# GBA_Modular_Matrix.net
KiCad netlist of a schematic drawn in EAGLE
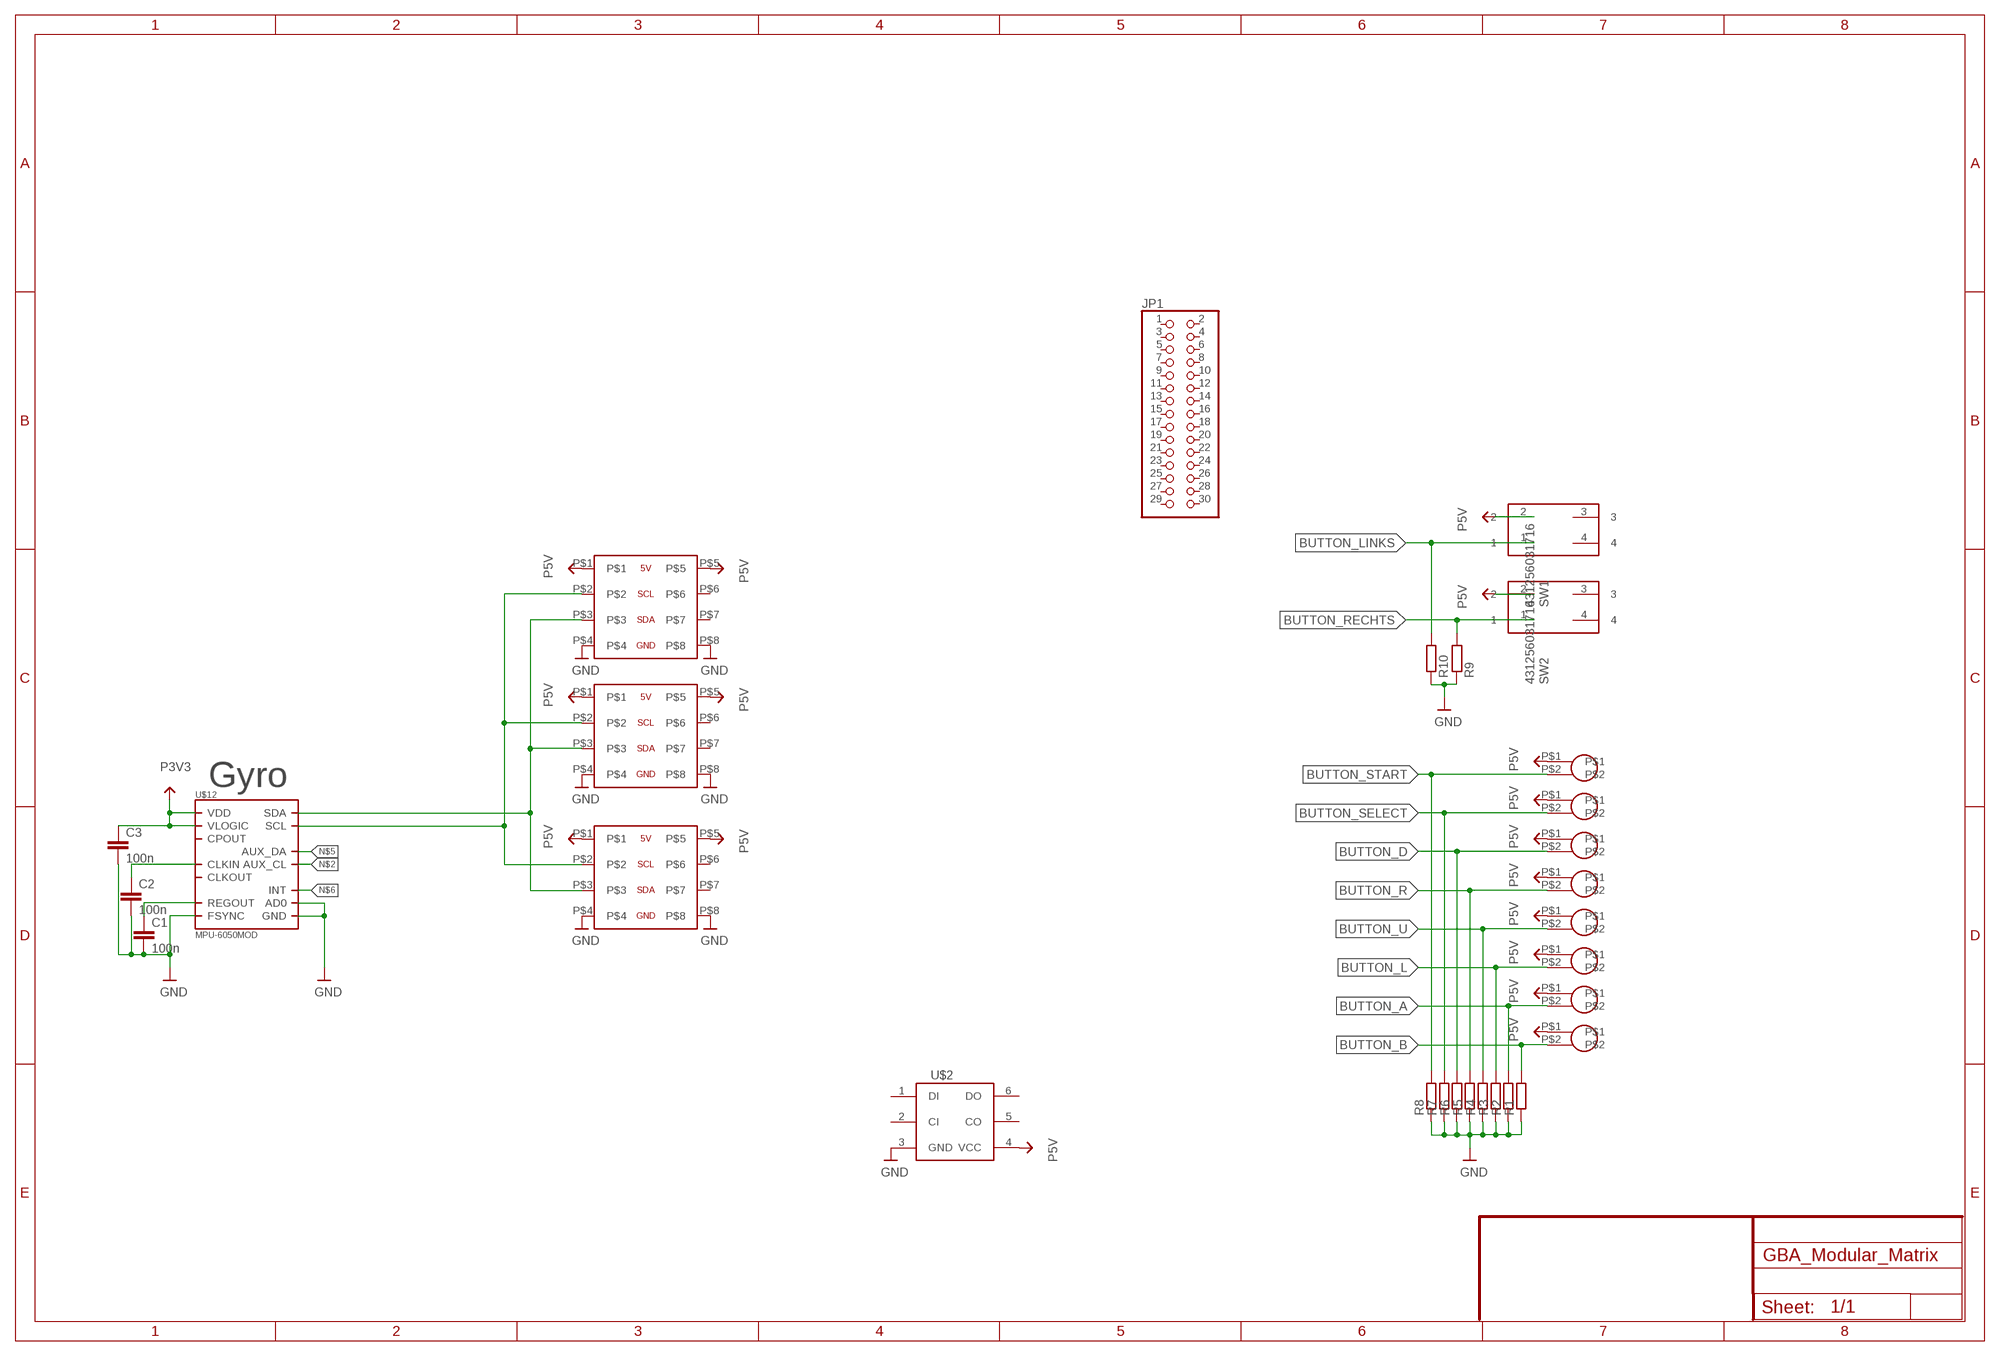
[diagram p0: schematic, sheet 1]

(export (version "E")
  (design (tool "Eeschema 10.0.6"))
  (components
    (comp (ref "C1")
      (value "100n")
      (footprint "eagle-import:C0603")
      (libsource (lib "eagle-import") (part "C-EUC0603"))
    )
    (comp (ref "C2")
      (value "100n")
      (footprint "eagle-import:C0603")
      (libsource (lib "eagle-import") (part "C-EUC0603"))
    )
    (comp (ref "C3")
      (value "100n")
      (footprint "eagle-import:C0603")
      (libsource (lib "eagle-import") (part "C-EUC0603"))
    )
    (comp (ref "JP1")
      (value "PINHD-2X15")
      (footprint "eagle-import:2X15")
      (libsource (lib "eagle-import") (part "PINHD-2X15"))
    )
    (comp (ref "R1")
      (value "R-EU_R0805")
      (footprint "eagle-import:R0805")
      (libsource (lib "eagle-import") (part "R-EU_R0805"))
    )
    (comp (ref "R2")
      (value "R-EU_R0805")
      (footprint "eagle-import:R0805")
      (libsource (lib "eagle-import") (part "R-EU_R0805"))
    )
    (comp (ref "R3")
      (value "R-EU_R0805")
      (footprint "eagle-import:R0805")
      (libsource (lib "eagle-import") (part "R-EU_R0805"))
    )
    (comp (ref "R4")
      (value "R-EU_R0805")
      (footprint "eagle-import:R0805")
      (libsource (lib "eagle-import") (part "R-EU_R0805"))
    )
    (comp (ref "R5")
      (value "R-EU_R0805")
      (footprint "eagle-import:R0805")
      (libsource (lib "eagle-import") (part "R-EU_R0805"))
    )
    (comp (ref "R6")
      (value "R-EU_R0805")
      (footprint "eagle-import:R0805")
      (libsource (lib "eagle-import") (part "R-EU_R0805"))
    )
    (comp (ref "R7")
      (value "R-EU_R0805")
      (footprint "eagle-import:R0805")
      (libsource (lib "eagle-import") (part "R-EU_R0805"))
    )
    (comp (ref "R8")
      (value "R-EU_R0805")
      (footprint "eagle-import:R0805")
      (libsource (lib "eagle-import") (part "R-EU_R0805"))
    )
    (comp (ref "R9")
      (value "R-EU_R0805")
      (footprint "eagle-import:R0805")
      (libsource (lib "eagle-import") (part "R-EU_R0805"))
    )
    (comp (ref "R10")
      (value "R-EU_R0805")
      (footprint "eagle-import:R0805")
      (libsource (lib "eagle-import") (part "R-EU_R0805"))
    )
    (comp (ref "SW1")
      (value "431256031716")
      (footprint "eagle-import:431256031716")
      (libsource (lib "eagle-import") (part "431256031716"))
    )
    (comp (ref "SW2")
      (value "431256031716")
      (footprint "eagle-import:431256031716")
      (libsource (lib "eagle-import") (part "431256031716"))
    )
    (comp (ref "U$2")
      (value "APA102")
      (footprint "eagle-import:LED5050")
      (libsource (lib "eagle-import") (part "APA102"))
    )
    (comp (ref "U$4")
      (value "GBA_BUTTONAB")
      (footprint "eagle-import:GBA_AB")
      (libsource (lib "eagle-import") (part "GBA_BUTTONAB"))
    )
    (comp (ref "U$5")
      (value "GBA_BUTTONAB")
      (footprint "eagle-import:GBA_AB")
      (libsource (lib "eagle-import") (part "GBA_BUTTONAB"))
    )
    (comp (ref "U$6")
      (value "GBA_BUTTONDIREKTION")
      (footprint "eagle-import:GBA_DIREKTION")
      (libsource (lib "eagle-import") (part "GBA_BUTTONDIREKTION"))
    )
    (comp (ref "U$7")
      (value "GBA_BUTTONDIREKTION")
      (footprint "eagle-import:GBA_DIREKTION")
      (libsource (lib "eagle-import") (part "GBA_BUTTONDIREKTION"))
    )
    (comp (ref "U$8")
      (value "GBA_BUTTONDIREKTION")
      (footprint "eagle-import:GBA_DIREKTION")
      (libsource (lib "eagle-import") (part "GBA_BUTTONDIREKTION"))
    )
    (comp (ref "U$9")
      (value "GBA_BUTTONDIREKTION")
      (footprint "eagle-import:GBA_DIREKTION")
      (libsource (lib "eagle-import") (part "GBA_BUTTONDIREKTION"))
    )
    (comp (ref "U$10")
      (value "GBA_BUTTONSTART")
      (footprint "eagle-import:GBA_START")
      (libsource (lib "eagle-import") (part "GBA_BUTTONSTART"))
    )
    (comp (ref "U$11")
      (value "GBA_BUTTONSTART")
      (footprint "eagle-import:GBA_START")
      (libsource (lib "eagle-import") (part "GBA_BUTTONSTART"))
    )
    (comp (ref "U$12")
      (value "MPU-6050MOD")
      (footprint "eagle-import:QFN.24.4X4.MOD")
      (libsource (lib "eagle-import") (part "MPU-6050MOD"))
    )
    (comp (ref "U$18")
      (value "DEBAUER_18X6MATRIX")
      (footprint "eagle-import:DEBAUER_16X8MATRIX")
      (libsource (lib "eagle-import") (part "DEBAUER_18X6MATRIX"))
    )
    (comp (ref "U$19")
      (value "DEBAUER_18X6MATRIX")
      (footprint "eagle-import:DEBAUER_16X8MATRIX")
      (libsource (lib "eagle-import") (part "DEBAUER_18X6MATRIX"))
    )
    (comp (ref "U$20")
      (value "DEBAUER_18X6MATRIX")
      (footprint "eagle-import:DEBAUER_16X8MATRIX")
      (libsource (lib "eagle-import") (part "DEBAUER_18X6MATRIX"))
    )
  )
  (nets
    (net (code "1") (name "BUTTON_A") (class "Default")
      (node (ref "R2") (pin "2") (pinfunction "2_2") (pintype "passive"))
      (node (ref "U$4") (pin "P$2") (pinfunction "P$2_P$2") (pintype "bidirectional"))
    )
    (net (code "2") (name "BUTTON_B") (class "Default")
      (node (ref "R1") (pin "2") (pinfunction "2_2") (pintype "passive"))
      (node (ref "U$5") (pin "P$2") (pinfunction "P$2_P$2") (pintype "bidirectional"))
    )
    (net (code "3") (name "BUTTON_D") (class "Default")
      (node (ref "R6") (pin "2") (pinfunction "2_2") (pintype "passive"))
      (node (ref "U$6") (pin "P$2") (pinfunction "P$2_P$2") (pintype "bidirectional"))
    )
    (net (code "4") (name "BUTTON_L") (class "Default")
      (node (ref "R3") (pin "2") (pinfunction "2_2") (pintype "passive"))
      (node (ref "U$9") (pin "P$2") (pinfunction "P$2_P$2") (pintype "bidirectional"))
    )
    (net (code "5") (name "BUTTON_LINKS") (class "Default")
      (node (ref "R10") (pin "2") (pinfunction "2_2") (pintype "passive"))
      (node (ref "SW1") (pin "1") (pinfunction "1_1") (pintype "bidirectional"))
    )
    (net (code "6") (name "BUTTON_R") (class "Default")
      (node (ref "R5") (pin "2") (pinfunction "2_2") (pintype "passive"))
      (node (ref "U$7") (pin "P$2") (pinfunction "P$2_P$2") (pintype "bidirectional"))
    )
    (net (code "7") (name "BUTTON_RECHTS") (class "Default")
      (node (ref "R9") (pin "2") (pinfunction "2_2") (pintype "passive"))
      (node (ref "SW2") (pin "1") (pinfunction "1_1") (pintype "bidirectional"))
    )
    (net (code "8") (name "BUTTON_SELECT") (class "Default")
      (node (ref "R7") (pin "2") (pinfunction "2_2") (pintype "passive"))
      (node (ref "U$11") (pin "P$2") (pinfunction "P$2_P$2") (pintype "bidirectional"))
    )
    (net (code "9") (name "BUTTON_START") (class "Default")
      (node (ref "R8") (pin "2") (pinfunction "2_2") (pintype "passive"))
      (node (ref "U$10") (pin "P$2") (pinfunction "P$2_P$2") (pintype "bidirectional"))
    )
    (net (code "10") (name "BUTTON_U") (class "Default")
      (node (ref "R4") (pin "2") (pinfunction "2_2") (pintype "passive"))
      (node (ref "U$8") (pin "P$2") (pinfunction "P$2_P$2") (pintype "bidirectional"))
    )
    (net (code "11") (name "GND") (class "Default")
      (node (ref "C1") (pin "2") (pinfunction "2_2") (pintype "passive"))
      (node (ref "C2") (pin "2") (pinfunction "2_2") (pintype "passive"))
      (node (ref "C3") (pin "2") (pinfunction "2_2") (pintype "passive"))
      (node (ref "R1") (pin "1") (pinfunction "1_1") (pintype "passive"))
      (node (ref "R10") (pin "1") (pinfunction "1_1") (pintype "passive"))
      (node (ref "R2") (pin "1") (pinfunction "1_1") (pintype "passive"))
      (node (ref "R3") (pin "1") (pinfunction "1_1") (pintype "passive"))
      (node (ref "R4") (pin "1") (pinfunction "1_1") (pintype "passive"))
      (node (ref "R5") (pin "1") (pinfunction "1_1") (pintype "passive"))
      (node (ref "R6") (pin "1") (pinfunction "1_1") (pintype "passive"))
      (node (ref "R7") (pin "1") (pinfunction "1_1") (pintype "passive"))
      (node (ref "R8") (pin "1") (pinfunction "1_1") (pintype "passive"))
      (node (ref "R9") (pin "1") (pinfunction "1_1") (pintype "passive"))
      (node (ref "U$12") (pin "11") (pinfunction "FSYNC_11") (pintype "bidirectional"))
      (node (ref "U$12") (pin "18") (pinfunction "GND_18") (pintype "bidirectional"))
      (node (ref "U$12") (pin "9") (pinfunction "AD0_9") (pintype "bidirectional"))
      (node (ref "U$18") (pin "P$4") (pinfunction "P$4_P$4") (pintype "bidirectional"))
      (node (ref "U$18") (pin "P$8") (pinfunction "P$8_P$8") (pintype "bidirectional"))
      (node (ref "U$19") (pin "P$4") (pinfunction "P$4_P$4") (pintype "bidirectional"))
      (node (ref "U$19") (pin "P$8") (pinfunction "P$8_P$8") (pintype "bidirectional"))
      (node (ref "U$2") (pin "3") (pinfunction "GND_3") (pintype "bidirectional"))
      (node (ref "U$20") (pin "P$4") (pinfunction "P$4_P$4") (pintype "bidirectional"))
      (node (ref "U$20") (pin "P$8") (pinfunction "P$8_P$8") (pintype "bidirectional"))
    )
    (net (code "12") (name "N$2") (class "Default")
      (node (ref "U$12") (pin "7") (pinfunction "AUX_CL_7") (pintype "bidirectional"))
    )
    (net (code "13") (name "N$5") (class "Default")
      (node (ref "U$12") (pin "6") (pinfunction "AUX_DA_6") (pintype "bidirectional"))
    )
    (net (code "14") (name "N$6") (class "Default")
      (node (ref "U$12") (pin "12") (pinfunction "INT_12") (pintype "bidirectional"))
    )
    (net (code "15") (name "Net-(U$12-CLKIN)") (class "Default")
      (node (ref "C2") (pin "1") (pinfunction "1_1") (pintype "passive"))
      (node (ref "U$12") (pin "1") (pinfunction "CLKIN_1") (pintype "bidirectional"))
    )
    (net (code "16") (name "Net-(U$12-REGOUT)") (class "Default")
      (node (ref "C1") (pin "1") (pinfunction "1_1") (pintype "passive"))
      (node (ref "U$12") (pin "10") (pinfunction "REGOUT_10") (pintype "bidirectional"))
    )
    (net (code "17") (name "Net-(U$12-SCL)") (class "Default")
      (node (ref "U$12") (pin "23") (pinfunction "SCL_23") (pintype "bidirectional"))
      (node (ref "U$18") (pin "P$2") (pinfunction "P$2_P$2") (pintype "bidirectional"))
      (node (ref "U$19") (pin "P$2") (pinfunction "P$2_P$2") (pintype "bidirectional"))
      (node (ref "U$20") (pin "P$2") (pinfunction "P$2_P$2") (pintype "bidirectional"))
    )
    (net (code "18") (name "Net-(U$12-SDA)") (class "Default")
      (node (ref "U$12") (pin "24") (pinfunction "SDA_24") (pintype "bidirectional"))
      (node (ref "U$18") (pin "P$3") (pinfunction "P$3_P$3") (pintype "bidirectional"))
      (node (ref "U$19") (pin "P$3") (pinfunction "P$3_P$3") (pintype "bidirectional"))
      (node (ref "U$20") (pin "P$3") (pinfunction "P$3_P$3") (pintype "bidirectional"))
    )
    (net (code "19") (name "P3V3") (class "Default")
      (node (ref "C3") (pin "1") (pinfunction "1_1") (pintype "passive"))
      (node (ref "U$12") (pin "13") (pinfunction "VDD_13") (pintype "bidirectional"))
      (node (ref "U$12") (pin "8") (pinfunction "VLOGIC_8") (pintype "bidirectional"))
    )
    (net (code "20") (name "P5V") (class "Default")
      (node (ref "SW1") (pin "2") (pinfunction "2_2") (pintype "bidirectional"))
      (node (ref "SW2") (pin "2") (pinfunction "2_2") (pintype "bidirectional"))
      (node (ref "U$10") (pin "P$1") (pinfunction "P$1_P$1") (pintype "bidirectional"))
      (node (ref "U$11") (pin "P$1") (pinfunction "P$1_P$1") (pintype "bidirectional"))
      (node (ref "U$18") (pin "P$1") (pinfunction "P$1_P$1") (pintype "bidirectional"))
      (node (ref "U$18") (pin "P$5") (pinfunction "P$5_P$5") (pintype "bidirectional"))
      (node (ref "U$19") (pin "P$1") (pinfunction "P$1_P$1") (pintype "bidirectional"))
      (node (ref "U$19") (pin "P$5") (pinfunction "P$5_P$5") (pintype "bidirectional"))
      (node (ref "U$2") (pin "4") (pinfunction "VCC_4") (pintype "bidirectional"))
      (node (ref "U$20") (pin "P$1") (pinfunction "P$1_P$1") (pintype "bidirectional"))
      (node (ref "U$20") (pin "P$5") (pinfunction "P$5_P$5") (pintype "bidirectional"))
      (node (ref "U$4") (pin "P$1") (pinfunction "P$1_P$1") (pintype "bidirectional"))
      (node (ref "U$5") (pin "P$1") (pinfunction "P$1_P$1") (pintype "bidirectional"))
      (node (ref "U$6") (pin "P$1") (pinfunction "P$1_P$1") (pintype "bidirectional"))
      (node (ref "U$7") (pin "P$1") (pinfunction "P$1_P$1") (pintype "bidirectional"))
      (node (ref "U$8") (pin "P$1") (pinfunction "P$1_P$1") (pintype "bidirectional"))
      (node (ref "U$9") (pin "P$1") (pinfunction "P$1_P$1") (pintype "bidirectional"))
    )
    (net (code "21") (name "unconnected-(JP1-Pad1)") (class "Default")
      (node (ref "JP1") (pin "1") (pinfunction "1_1") (pintype "passive"))
    )
    (net (code "22") (name "unconnected-(JP1-Pad2)") (class "Default")
      (node (ref "JP1") (pin "2") (pinfunction "2_2") (pintype "passive"))
    )
    (net (code "23") (name "unconnected-(JP1-Pad3)") (class "Default")
      (node (ref "JP1") (pin "3") (pinfunction "3_3") (pintype "passive"))
    )
    (net (code "24") (name "unconnected-(JP1-Pad4)") (class "Default")
      (node (ref "JP1") (pin "4") (pinfunction "4_4") (pintype "passive"))
    )
    (net (code "25") (name "unconnected-(JP1-Pad5)") (class "Default")
      (node (ref "JP1") (pin "5") (pinfunction "5_5") (pintype "passive"))
    )
    (net (code "26") (name "unconnected-(JP1-Pad6)") (class "Default")
      (node (ref "JP1") (pin "6") (pinfunction "6_6") (pintype "passive"))
    )
    (net (code "27") (name "unconnected-(JP1-Pad7)") (class "Default")
      (node (ref "JP1") (pin "7") (pinfunction "7_7") (pintype "passive"))
    )
    (net (code "28") (name "unconnected-(JP1-Pad8)") (class "Default")
      (node (ref "JP1") (pin "8") (pinfunction "8_8") (pintype "passive"))
    )
    (net (code "29") (name "unconnected-(JP1-Pad9)") (class "Default")
      (node (ref "JP1") (pin "9") (pinfunction "9_9") (pintype "passive"))
    )
    (net (code "30") (name "unconnected-(JP1-Pad10)") (class "Default")
      (node (ref "JP1") (pin "10") (pinfunction "10_10") (pintype "passive"))
    )
    (net (code "31") (name "unconnected-(JP1-Pad11)") (class "Default")
      (node (ref "JP1") (pin "11") (pinfunction "11_11") (pintype "passive"))
    )
    (net (code "32") (name "unconnected-(JP1-Pad12)") (class "Default")
      (node (ref "JP1") (pin "12") (pinfunction "12_12") (pintype "passive"))
    )
    (net (code "33") (name "unconnected-(JP1-Pad13)") (class "Default")
      (node (ref "JP1") (pin "13") (pinfunction "13_13") (pintype "passive"))
    )
    (net (code "34") (name "unconnected-(JP1-Pad14)") (class "Default")
      (node (ref "JP1") (pin "14") (pinfunction "14_14") (pintype "passive"))
    )
    (net (code "35") (name "unconnected-(JP1-Pad15)") (class "Default")
      (node (ref "JP1") (pin "15") (pinfunction "15_15") (pintype "passive"))
    )
    (net (code "36") (name "unconnected-(JP1-Pad16)") (class "Default")
      (node (ref "JP1") (pin "16") (pinfunction "16_16") (pintype "passive"))
    )
    (net (code "37") (name "unconnected-(JP1-Pad17)") (class "Default")
      (node (ref "JP1") (pin "17") (pinfunction "17_17") (pintype "passive"))
    )
    (net (code "38") (name "unconnected-(JP1-Pad18)") (class "Default")
      (node (ref "JP1") (pin "18") (pinfunction "18_18") (pintype "passive"))
    )
    (net (code "39") (name "unconnected-(JP1-Pad19)") (class "Default")
      (node (ref "JP1") (pin "19") (pinfunction "19_19") (pintype "passive"))
    )
    (net (code "40") (name "unconnected-(JP1-Pad20)") (class "Default")
      (node (ref "JP1") (pin "20") (pinfunction "20_20") (pintype "passive"))
    )
    (net (code "41") (name "unconnected-(JP1-Pad21)") (class "Default")
      (node (ref "JP1") (pin "21") (pinfunction "21_21") (pintype "passive"))
    )
    (net (code "42") (name "unconnected-(JP1-Pad22)") (class "Default")
      (node (ref "JP1") (pin "22") (pinfunction "22_22") (pintype "passive"))
    )
    (net (code "43") (name "unconnected-(JP1-Pad23)") (class "Default")
      (node (ref "JP1") (pin "23") (pinfunction "23_23") (pintype "passive"))
    )
    (net (code "44") (name "unconnected-(JP1-Pad24)") (class "Default")
      (node (ref "JP1") (pin "24") (pinfunction "24_24") (pintype "passive"))
    )
    (net (code "45") (name "unconnected-(JP1-Pad25)") (class "Default")
      (node (ref "JP1") (pin "25") (pinfunction "25_25") (pintype "passive"))
    )
    (net (code "46") (name "unconnected-(JP1-Pad26)") (class "Default")
      (node (ref "JP1") (pin "26") (pinfunction "26_26") (pintype "passive"))
    )
    (net (code "47") (name "unconnected-(JP1-Pad27)") (class "Default")
      (node (ref "JP1") (pin "27") (pinfunction "27_27") (pintype "passive"))
    )
    (net (code "48") (name "unconnected-(JP1-Pad28)") (class "Default")
      (node (ref "JP1") (pin "28") (pinfunction "28_28") (pintype "passive"))
    )
    (net (code "49") (name "unconnected-(JP1-Pad29)") (class "Default")
      (node (ref "JP1") (pin "29") (pinfunction "29_29") (pintype "passive"))
    )
    (net (code "50") (name "unconnected-(JP1-Pad30)") (class "Default")
      (node (ref "JP1") (pin "30") (pinfunction "30_30") (pintype "passive"))
    )
    (net (code "51") (name "unconnected-(SW1-Pad3)") (class "Default")
      (node (ref "SW1") (pin "3") (pinfunction "3_3") (pintype "bidirectional"))
    )
    (net (code "52") (name "unconnected-(SW1-Pad4)") (class "Default")
      (node (ref "SW1") (pin "4") (pinfunction "4_4") (pintype "bidirectional"))
    )
    (net (code "53") (name "unconnected-(SW2-Pad3)") (class "Default")
      (node (ref "SW2") (pin "3") (pinfunction "3_3") (pintype "bidirectional"))
    )
    (net (code "54") (name "unconnected-(SW2-Pad4)") (class "Default")
      (node (ref "SW2") (pin "4") (pinfunction "4_4") (pintype "bidirectional"))
    )
    (net (code "55") (name "unconnected-(U$2-CI-Pad2)") (class "Default")
      (node (ref "U$2") (pin "2") (pinfunction "CI_2") (pintype "bidirectional"))
    )
    (net (code "56") (name "unconnected-(U$2-CO-Pad5)") (class "Default")
      (node (ref "U$2") (pin "5") (pinfunction "CO_5") (pintype "bidirectional"))
    )
    (net (code "57") (name "unconnected-(U$2-DI-Pad1)") (class "Default")
      (node (ref "U$2") (pin "1") (pinfunction "DI_1") (pintype "bidirectional"))
    )
    (net (code "58") (name "unconnected-(U$2-DO-Pad6)") (class "Default")
      (node (ref "U$2") (pin "6") (pinfunction "DO_6") (pintype "bidirectional"))
    )
    (net (code "59") (name "unconnected-(U$12-CLKOUT-Pad22)") (class "Default")
      (node (ref "U$12") (pin "22") (pinfunction "CLKOUT_22") (pintype "bidirectional"))
    )
    (net (code "60") (name "unconnected-(U$12-CPOUT-Pad20)") (class "Default")
      (node (ref "U$12") (pin "20") (pinfunction "CPOUT_20") (pintype "bidirectional"))
    )
    (net (code "61") (name "unconnected-(U$18-PadP$6)") (class "Default")
      (node (ref "U$18") (pin "P$6") (pinfunction "P$6_P$6") (pintype "bidirectional"))
    )
    (net (code "62") (name "unconnected-(U$18-PadP$7)") (class "Default")
      (node (ref "U$18") (pin "P$7") (pinfunction "P$7_P$7") (pintype "bidirectional"))
    )
    (net (code "63") (name "unconnected-(U$19-PadP$6)") (class "Default")
      (node (ref "U$19") (pin "P$6") (pinfunction "P$6_P$6") (pintype "bidirectional"))
    )
    (net (code "64") (name "unconnected-(U$19-PadP$7)") (class "Default")
      (node (ref "U$19") (pin "P$7") (pinfunction "P$7_P$7") (pintype "bidirectional"))
    )
    (net (code "65") (name "unconnected-(U$20-PadP$6)") (class "Default")
      (node (ref "U$20") (pin "P$6") (pinfunction "P$6_P$6") (pintype "bidirectional"))
    )
    (net (code "66") (name "unconnected-(U$20-PadP$7)") (class "Default")
      (node (ref "U$20") (pin "P$7") (pinfunction "P$7_P$7") (pintype "bidirectional"))
    )
  )
)
